# keyboard.net
KiCad netlist of a schematic drawn in Altium Designer
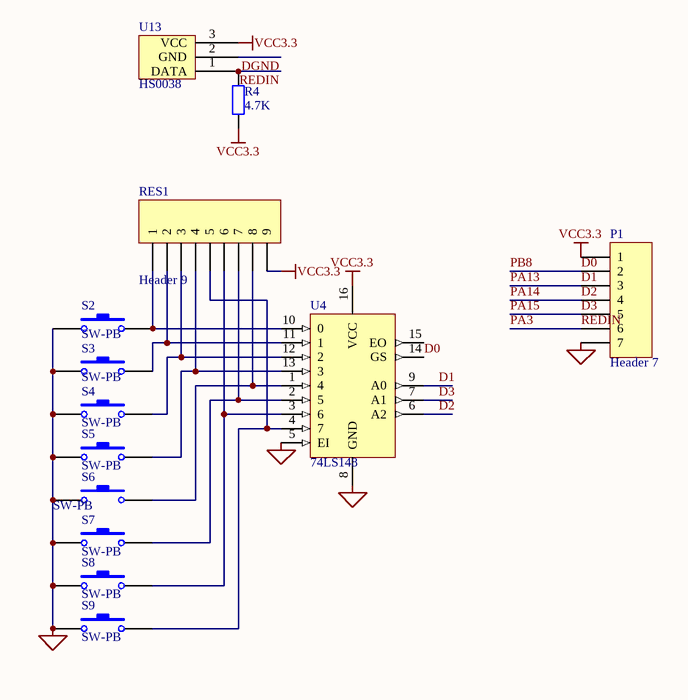
[diagram p0: keyboard.SchDoc]

(export (version "E")
  (design (tool "Eeschema 10.0.6"))
  (components
    (comp (ref "P1")
      (value "Header 7")
      (footprint "HDR1X7")
      (description "Header, 7-Pin")
      (fields (field (name "PUBLISHER") "Altium Limited"))
      (libsource (lib "Miscellaneous Connectors") (part "Header 7"))
    )
    (comp (ref "R4")
      (value "4.7K")
      (footprint "1608[0603]")
      (description "Resistor")
      (fields (field (name "PUBLISHER") "Altium Limited"))
      (libsource (lib "Miscellaneous Devices") (part "Res2"))
    )
    (comp (ref "RES1")
      (value "Header 9")
      (footprint "HDR1X9")
      (description "Header, 9-Pin")
      (fields (field (name "PUBLISHER") "Altium Limited"))
      (libsource (lib "Miscellaneous Connectors") (part "Header 9"))
    )
    (comp (ref "S2")
      (value "SW-PB")
      (footprint "SW")
      (description "Switch")
      (fields (field (name "PUBLISHER") "Altium Limited"))
      (libsource (lib "") (part "SW-PB_1"))
    )
    (comp (ref "S3")
      (value "SW-PB")
      (footprint "SW")
      (description "Switch")
      (fields (field (name "PUBLISHER") "Altium Limited"))
      (libsource (lib "") (part "SW-PB_1"))
    )
    (comp (ref "S4")
      (value "SW-PB")
      (footprint "SW")
      (description "Switch")
      (fields (field (name "PUBLISHER") "Altium Limited"))
      (libsource (lib "") (part "SW-PB_1"))
    )
    (comp (ref "S5")
      (value "SW-PB")
      (footprint "SW")
      (description "Switch")
      (fields (field (name "PUBLISHER") "Altium Limited"))
      (libsource (lib "Miscellaneous Devices") (part "SW-PB"))
    )
    (comp (ref "S6")
      (value "SW-PB")
      (footprint "AN12")
      (description "Switch")
      (fields (field (name "PUBLISHER") "Altium Limited"))
      (libsource (lib "") (part "SW-PB_1"))
    )
    (comp (ref "S7")
      (value "SW-PB")
      (footprint "AN12")
      (description "Switch")
      (fields (field (name "PUBLISHER") "Altium Limited"))
      (libsource (lib "") (part "SW-PB_1"))
    )
    (comp (ref "S8")
      (value "SW-PB")
      (footprint "AN12")
      (description "Switch")
      (fields (field (name "PUBLISHER") "Altium Limited"))
      (libsource (lib "") (part "SW-PB_1"))
    )
    (comp (ref "S9")
      (value "SW-PB")
      (footprint "AN12")
      (description "Switch")
      (fields (field (name "PUBLISHER") "Altium Limited"))
      (libsource (lib "") (part "SW-PB_1"))
    )
    (comp (ref "U4")
      (value "74LS148")
      (footprint "DIP-16")
      (description "8-Line to 3-Line Priority Encoder")
      (libsource (lib "TTL74系列") (part "74LS148"))
    )
    (comp (ref "U13") (value "HS0038") (footprint "HS0038") (libsource (lib "selfmade") (part "HS0038")))
  )
  (nets
    (net (code "1") (name "/D0") (class "Default")
      (node (ref "P1") (pin "2") (pinfunction "2_2") (pintype "passive"))
      (node (ref "U4") (pin "14") (pinfunction "GS_14") (pintype "output"))
    )
    (net (code "2") (name "/D1") (class "Default")
      (node (ref "P1") (pin "3") (pinfunction "3_3") (pintype "passive"))
      (node (ref "U4") (pin "9") (pinfunction "A0_9") (pintype "output"))
    )
    (net (code "3") (name "/D2") (class "Default")
      (node (ref "P1") (pin "4") (pinfunction "4_4") (pintype "passive"))
      (node (ref "U4") (pin "6") (pinfunction "A2_6") (pintype "output"))
    )
    (net (code "4") (name "/D3") (class "Default")
      (node (ref "P1") (pin "5") (pinfunction "5_5") (pintype "passive"))
      (node (ref "U4") (pin "7") (pinfunction "A1_7") (pintype "output"))
    )
    (net (code "5") (name "/PA3") (class "Default")
      (node (ref "P1") (pin "6") (pinfunction "6_6") (pintype "passive"))
      (node (ref "R4") (pin "1") (pinfunction "1_1") (pintype "passive"))
      (node (ref "U13") (pin "1") (pinfunction "DATA_1") (pintype "passive"))
    )
    (net (code "6") (name "DGND") (class "Default")
      (node (ref "P1") (pin "7") (pinfunction "7_7") (pintype "passive"))
      (node (ref "S2") (pin "1") (pinfunction "1_1") (pintype "passive"))
      (node (ref "S3") (pin "1") (pinfunction "1_1") (pintype "passive"))
      (node (ref "S4") (pin "1") (pinfunction "1_1") (pintype "passive"))
      (node (ref "S5") (pin "4") (pinfunction "4_4") (pintype "passive"))
      (node (ref "S6") (pin "1") (pinfunction "1_1") (pintype "passive"))
      (node (ref "S7") (pin "1") (pinfunction "1_1") (pintype "passive"))
      (node (ref "S8") (pin "1") (pinfunction "1_1") (pintype "passive"))
      (node (ref "S9") (pin "1") (pinfunction "1_1") (pintype "passive"))
      (node (ref "U13") (pin "2") (pinfunction "GND_2") (pintype "passive"))
      (node (ref "U4") (pin "5") (pinfunction "EI_5") (pintype "input"))
      (node (ref "U4") (pin "8") (pinfunction "GND_8") (pintype "power_in"))
    )
    (net (code "7") (name "Net-(U4-0)") (class "Default")
      (node (ref "RES1") (pin "1") (pinfunction "1_1") (pintype "passive"))
      (node (ref "S2") (pin "2") (pinfunction "2_2") (pintype "passive"))
      (node (ref "U4") (pin "10") (pinfunction "0_10") (pintype "input"))
    )
    (net (code "8") (name "Net-(U4-1)") (class "Default")
      (node (ref "RES1") (pin "2") (pinfunction "2_2") (pintype "passive"))
      (node (ref "S3") (pin "2") (pinfunction "2_2") (pintype "passive"))
      (node (ref "U4") (pin "11") (pinfunction "1_11") (pintype "input"))
    )
    (net (code "9") (name "Net-(U4-2)") (class "Default")
      (node (ref "RES1") (pin "3") (pinfunction "3_3") (pintype "passive"))
      (node (ref "S4") (pin "2") (pinfunction "2_2") (pintype "passive"))
      (node (ref "U4") (pin "12") (pinfunction "2_12") (pintype "input"))
    )
    (net (code "10") (name "Net-(U4-3)") (class "Default")
      (node (ref "RES1") (pin "4") (pinfunction "4_4") (pintype "passive"))
      (node (ref "S5") (pin "2") (pinfunction "2_2") (pintype "passive"))
      (node (ref "U4") (pin "13") (pinfunction "3_13") (pintype "input"))
    )
    (net (code "11") (name "Net-(U4-4)") (class "Default")
      (node (ref "RES1") (pin "8") (pinfunction "8_8") (pintype "passive"))
      (node (ref "S6") (pin "2") (pinfunction "2_2") (pintype "passive"))
      (node (ref "U4") (pin "1") (pinfunction "4_1") (pintype "input"))
    )
    (net (code "12") (name "Net-(U4-5)") (class "Default")
      (node (ref "RES1") (pin "7") (pinfunction "7_7") (pintype "passive"))
      (node (ref "S7") (pin "2") (pinfunction "2_2") (pintype "passive"))
      (node (ref "U4") (pin "2") (pinfunction "5_2") (pintype "input"))
    )
    (net (code "13") (name "Net-(U4-6)") (class "Default")
      (node (ref "RES1") (pin "6") (pinfunction "6_6") (pintype "passive"))
      (node (ref "S8") (pin "2") (pinfunction "2_2") (pintype "passive"))
      (node (ref "U4") (pin "3") (pinfunction "6_3") (pintype "input"))
    )
    (net (code "14") (name "Net-(U4-7)") (class "Default")
      (node (ref "RES1") (pin "5") (pinfunction "5_5") (pintype "passive"))
      (node (ref "S9") (pin "2") (pinfunction "2_2") (pintype "passive"))
      (node (ref "U4") (pin "4") (pinfunction "7_4") (pintype "input"))
    )
    (net (code "15") (name "VCC3.3") (class "Default")
      (node (ref "P1") (pin "1") (pinfunction "1_1") (pintype "passive"))
      (node (ref "R4") (pin "2") (pinfunction "2_2") (pintype "passive"))
      (node (ref "RES1") (pin "9") (pinfunction "9_9") (pintype "passive"))
      (node (ref "U13") (pin "3") (pinfunction "VCC_3") (pintype "passive"))
      (node (ref "U4") (pin "16") (pinfunction "VCC_16") (pintype "power_in"))
    )
    (net (code "16") (name "unconnected-(U4-EO-Pad15)") (class "Default")
      (node (ref "U4") (pin "15") (pinfunction "EO_15") (pintype "output"))
    )
  )
)
